# Interface_-_USB-C.net
KiCad netlist of a schematic drawn in Altium Designer
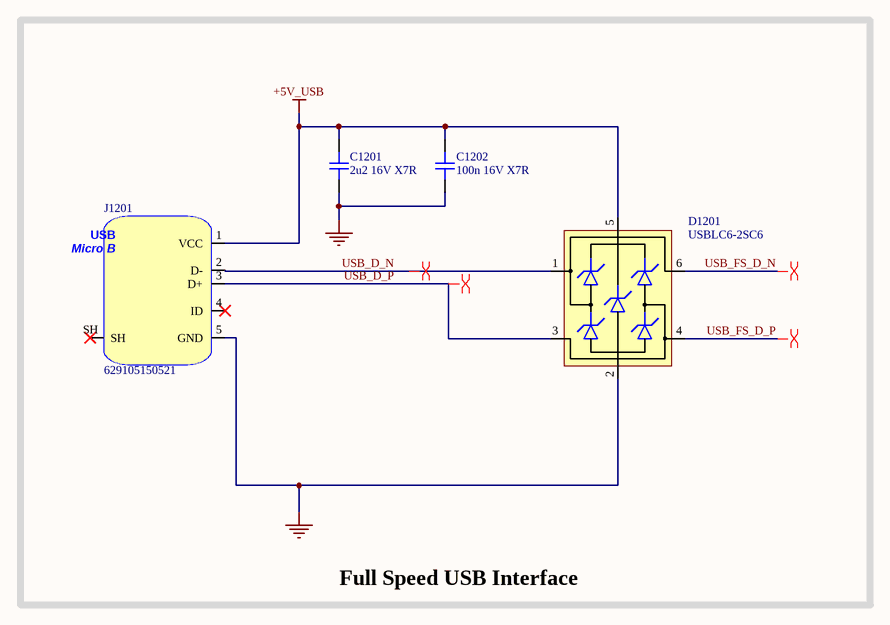
[diagram p0: Interface - USB-C.SchDoc]

(export (version "E")
  (design (tool "Eeschema 10.0.6"))
  (components
    (comp (ref "C1201")
      (value "2u2 16V X7R")
      (footprint "CAP_0603")
      (description "Capacitor SMD 0603")
      (fields
        (field (name "MANUFACTURER") "YAGEO")
        (field (name "MANUFACTURER PART NUMBER") "CC0603KRX7R7BB225")
      )
      (libsource (lib "Schematic-Lib-PhilsLab") (part "CAP_0603"))
    )
    (comp (ref "C1202")
      (value "100n 16V X7R")
      (footprint "CAP_0402")
      (description "Capacitor SMD 0402")
      (fields
        (field (name "MANUFACTURER") "YAGEO")
        (field (name "MANUFACTURER PART NUMBER") "CC0402JRX7R7BB104")
      )
      (libsource (lib "Schematic-Lib-PhilsLab") (part "CAP_0402"))
    )
    (comp (ref "D1201")
      (value "USBLC6-2SC6")
      (footprint "SOT-23-6")
      (description "Low-Capacitance ESD Protection USB")
      (fields (field (name "MANUFACTURER") "STMicroelectronics"))
      (libsource (lib "Schematic-Lib-PhilsLab") (part "USBLC6-2SC6"))
    )
    (comp (ref "J1201")
      (value "629105150521")
      (footprint "629105150521")
      (description "USB Connector Type Micro B 2.0 SMD")
      (fields (field (name "MANUFACTURER") "Wurth"))
      (libsource (lib "Schematic-Lib") (part "629105150521"))
    )
  )
  (nets
    (net (code "1") (name "+5V_USB") (class "Default")
      (node (ref "C1201") (pin "2") (pinfunction "2_2") (pintype "passive"))
      (node (ref "C1202") (pin "2") (pinfunction "2_2") (pintype "passive"))
      (node (ref "D1201") (pin "5") (pinfunction "VBUS_5") (pintype "power_in"))
      (node (ref "J1201") (pin "1") (pinfunction "VCC_1") (pintype "passive"))
    )
    (net (code "2") (name "/USB_D_N") (class "Default")
      (node (ref "D1201") (pin "1") (pinfunction "IO1_1") (pintype "bidirectional"))
      (node (ref "J1201") (pin "2") (pinfunction "D-_2") (pintype "passive"))
    )
    (net (code "3") (name "/USB_D_P") (class "Default")
      (node (ref "D1201") (pin "3") (pinfunction "IO2_3") (pintype "bidirectional"))
      (node (ref "J1201") (pin "3") (pinfunction "D+_3") (pintype "passive"))
    )
    (net (code "4") (name "/USB_FS_D_N") (class "Default")
      (node (ref "D1201") (pin "6") (pinfunction "IO1_6") (pintype "bidirectional"))
    )
    (net (code "5") (name "/USB_FS_D_P") (class "Default")
      (node (ref "D1201") (pin "4") (pinfunction "IO2_4") (pintype "bidirectional"))
    )
    (net (code "6") (name "GND") (class "Default")
      (node (ref "C1201") (pin "1") (pinfunction "1_1") (pintype "passive"))
      (node (ref "C1202") (pin "1") (pinfunction "1_1") (pintype "passive"))
      (node (ref "D1201") (pin "2") (pinfunction "GND_2") (pintype "power_in"))
      (node (ref "J1201") (pin "5") (pinfunction "GND_5") (pintype "passive"))
    )
    (net (code "7") (name "unconnected-(J1201-ID-Pad4)") (class "Default")
      (node (ref "J1201") (pin "4") (pinfunction "ID_4") (pintype "passive+no_connect"))
    )
    (net (code "8") (name "unconnected-(J1201-PadSH)") (class "Default")
      (node (ref "J1201") (pin "SH") (pinfunction "SH_SH") (pintype "passive+no_connect"))
    )
  )
)
